# InclinometerPower.net
KiCad netlist of a schematic drawn in Altium Designer
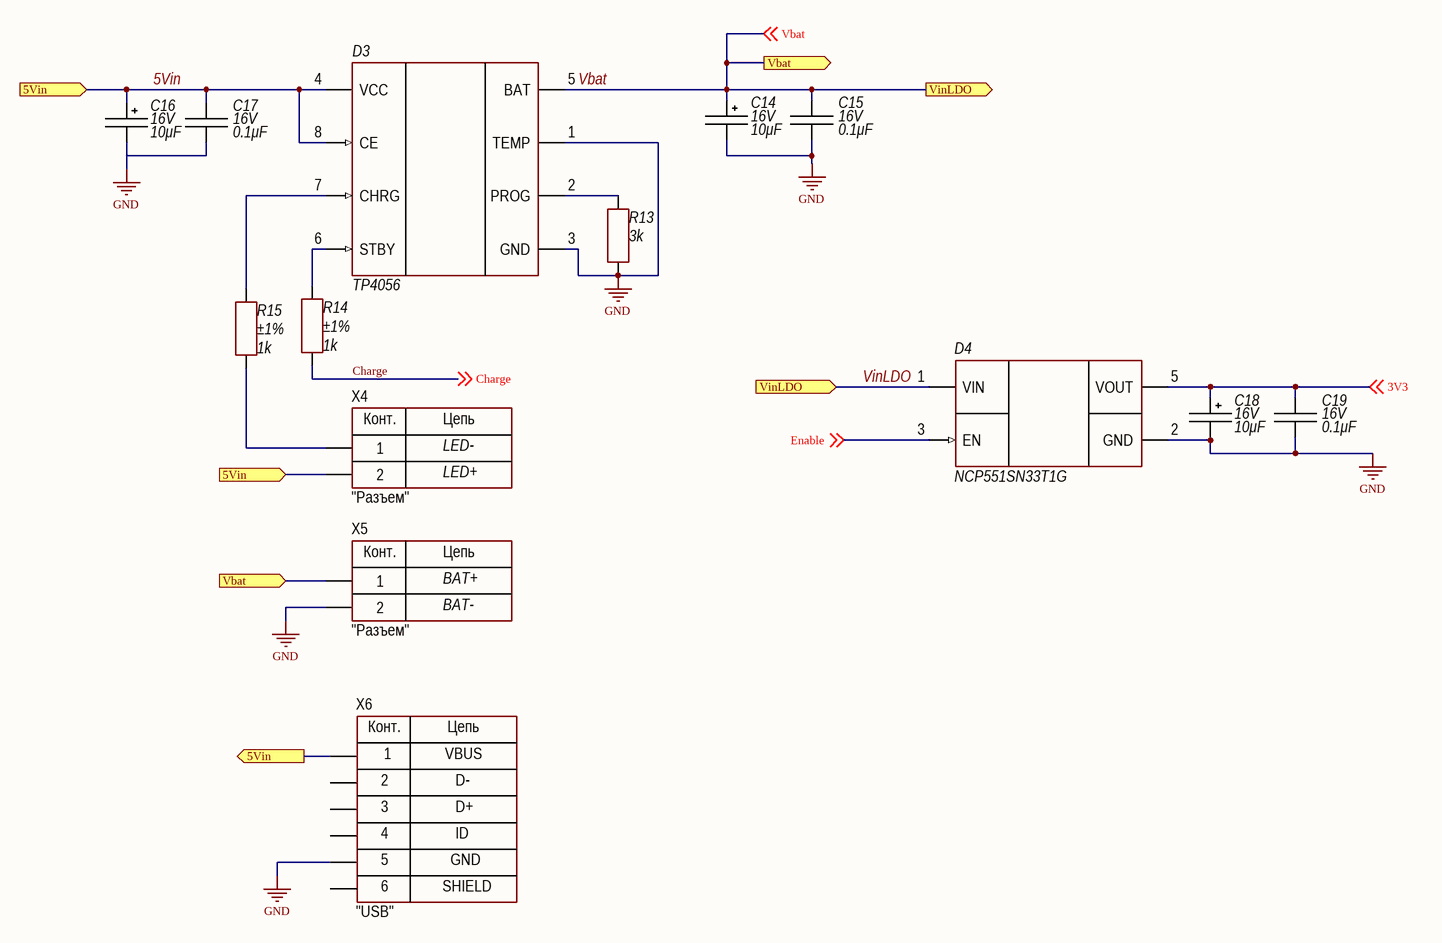
[diagram p0: InclinometerPower.SchDoc]

(export (version "E")
  (design (tool "Eeschema 10.0.6"))
  (components
    (comp (ref "C14")
      (value "10μF")
      (footprint "CAP: TANTAL-A")
      (fields
        (field (name "MANUFACTURER") "AVX")
        (field (name "PARTNUMBER") "TAJA106K016RNJ")
        (field (name "VALUEMANUFACTURERPARTNUMBER") "Tantalum capacitor, 10μF, 16V, ±10%, 3Ohm, case A (3216), -55...+125°C")
        (field (name "VOLTAGE") "16V")
      )
      (libsource (lib "") (part "Tantal_A_1"))
    )
    (comp (ref "C15")
      (value "0.1μF")
      (footprint "CAP: 0603")
      (fields
        (field (name "MANUFACTURER") "Murata Electronics")
        (field (name "PARTNUMBER") "GRM188R71C104KA01D")
        (field (name "VALUEMANUFACTURERPARTNUMBER") "Ceramic capacitor, 0.1μF, X7R, ±10%, 16V, 0603, -55...+125°C")
        (field (name "VOLTAGE") "16V")
      )
      (libsource (lib "") (part "Ceramic_0603_1"))
    )
    (comp (ref "C16")
      (value "10μF")
      (footprint "CAP: TANTAL-A")
      (fields
        (field (name "MANUFACTURER") "AVX")
        (field (name "PARTNUMBER") "TAJA106K016RNJ")
        (field (name "VALUEMANUFACTURERPARTNUMBER") "Tantalum capacitor, 10μF, 16V, ±10%, 3Ohm, case A (3216), -55...+125°C")
        (field (name "VOLTAGE") "16V")
      )
      (libsource (lib "Capacitor") (part "Tantal_A"))
    )
    (comp (ref "C17")
      (value "0.1μF")
      (footprint "CAP: 0603")
      (fields
        (field (name "MANUFACTURER") "Murata Electronics")
        (field (name "PARTNUMBER") "GRM188R71C104KA01D")
        (field (name "VALUEMANUFACTURERPARTNUMBER") "Ceramic capacitor, 0.1μF, X7R, ±10%, 16V, 0603, -55...+125°C")
        (field (name "VOLTAGE") "16V")
      )
      (libsource (lib "Capacitor") (part "Ceramic_0603"))
    )
    (comp (ref "C18")
      (value "10μF")
      (footprint "CAP: TANTAL-A")
      (fields
        (field (name "MANUFACTURER") "AVX")
        (field (name "PARTNUMBER") "TAJA106K016RNJ")
        (field (name "VALUEMANUFACTURERPARTNUMBER") "Tantalum capacitor, 10μF, 16V, ±10%, 3Ohm, case A (3216), -55...+125°C")
        (field (name "VOLTAGE") "16V")
      )
      (libsource (lib "") (part "Tantal_A_1"))
    )
    (comp (ref "C19")
      (value "0.1μF")
      (footprint "CAP: 0603")
      (fields
        (field (name "MANUFACTURER") "Murata Electronics")
        (field (name "PARTNUMBER") "GRM188R71C104KA01D")
        (field (name "VALUEMANUFACTURERPARTNUMBER") "Ceramic capacitor, 0.1μF, X7R, ±10%, 16V, 0603, -55...+125°C")
        (field (name "VOLTAGE") "16V")
      )
      (libsource (lib "") (part "Ceramic_0603_1"))
    )
    (comp (ref "D3")
      (value "~")
      (footprint "SOP8")
      (description "Linear Li-lon Battery Charger")
      (fields
        (field (name "MANUFACTURER") "Top Power")
        (field (name "VALUEMANUFACTURERPARTNUMBER") "Linear Li-lon Battery Charger, , , , 1A, -40...+85°C, SOP-8")
        (field (name "PARTNUMBER") "TP4056")
      )
      (libsource (lib "IC. Power supply") (part "TP4056"))
    )
    (comp (ref "D4")
      (value "~")
      (footprint "5-TSOP")
      (description "Linear voltage regulator")
      (fields
        (field (name "MANUFACTURER") "ON Semiconductor")
        (field (name "VALUEMANUFACTURERPARTNUMBER") "Linear voltage regulator, input 0...12V, 0.25V, output 3.3V, 150mA, -40...+85°C, TSOP-5")
        (field (name "PARTNUMBER") "NCP551SN33T1G")
      )
      (libsource (lib "IC. Power supply") (part "NCP551SN33T1G"))
    )
    (comp (ref "R13")
      (value "3k")
      (footprint "RES: 0603")
      (fields
        (field (name "MANUFACTURER") "Yageo")
        (field (name "PARTNUMBER") "RC0603FR-073KL")
        (field (name "VALUEMANUFACTURERPARTNUMBER") "Resistor film, 3k, ±1%, 0603, 0.1W, -55...+155°C")
      )
      (libsource (lib "Resistor") (part "Resistor_0603"))
    )
    (comp (ref "R14")
      (value "1k")
      (footprint "RES: 0603")
      (fields
        (field (name "MANUFACTURER") "Yageo")
        (field (name "PARTNUMBER") "RC0603FR-071KL")
        (field (name "VALUEMANUFACTURERPARTNUMBER") "Resistor film, 1k, ±1%, 0603, 0.1W, -55...+155°C")
        (field (name "TOLERANCE") "±1%")
      )
      (libsource (lib "") (part "Resistor_0603_1"))
    )
    (comp (ref "R15")
      (value "1k")
      (footprint "RES: 0603")
      (fields
        (field (name "MANUFACTURER") "Yageo")
        (field (name "PARTNUMBER") "RC0603FR-071KL")
        (field (name "VALUEMANUFACTURERPARTNUMBER") "Resistor film, 1k, ±1%, 0603, 0.1W, -55...+155°C")
        (field (name "TOLERANCE") "±1%")
      )
      (libsource (lib "Resistor") (part "Resistor_0603"))
    )
    (comp (ref "X4")
      (value "~")
      (footprint "CON: PLS-2")
      (fields
        (field (name "MANUFACTURER") "Connfly")
        (field (name "VALUEMANUFACTURERPARTNUMBER") "Connector, 2pin, 2.54mm, 500VAC, 3A")
        (field (name "PARTNUMBER") "PLS-2")
        (field (name "COMMENTTEXT") "\"Разъем\"")
      )
      (libsource (lib "Connector") (part "PLS-2"))
    )
    (comp (ref "X5")
      (value "~")
      (footprint "CON: PLS-2")
      (fields
        (field (name "MANUFACTURER") "Connfly")
        (field (name "VALUEMANUFACTURERPARTNUMBER") "Connector, 2pin, 2.54mm, 500VAC, 3A")
        (field (name "PARTNUMBER") "PLS-2")
        (field (name "COMMENTTEXT") "\"Разъем\"")
      )
      (libsource (lib "Connector") (part "PLS-2"))
    )
    (comp (ref "X6")
      (value "~")
      (footprint "CON: USB micro-A (ZX62-B-5PA)")
      (fields
        (field (name "MANUFACTURER") "Hirose Electric")
        (field (name "VALUEMANUFACTURERPARTNUMBER") "USB micro B")
        (field (name "PARTNUMBER") "ZX62-B-5PA")
        (field (name "COMMENTTEXT") "\"USB\"")
      )
      (libsource (lib "Connector") (part "Connector_USB_micro_B"))
    )
  )
  (nets
    (net (code "1") (name "/5Vin") (class "Default")
      (node (ref "C16") (pin "1") (pinfunction "1_1") (pintype "power_in"))
      (node (ref "C17") (pin "2") (pinfunction "2_2") (pintype "power_in"))
      (node (ref "D3") (pin "4") (pinfunction "VCC_4") (pintype "power_in"))
      (node (ref "D3") (pin "8") (pinfunction "CE_8") (pintype "input"))
      (node (ref "X4") (pin "2") (pinfunction "2_2") (pintype "passive"))
      (node (ref "X6") (pin "1") (pintype "passive"))
    )
    (net (code "2") (name "3V3") (class "Default")
      (node (ref "C18") (pin "1") (pinfunction "1_1") (pintype "power_in"))
      (node (ref "C19") (pin "2") (pinfunction "2_2") (pintype "power_in"))
      (node (ref "D4") (pin "5") (pinfunction "VOUT_5") (pintype "power_in"))
    )
    (net (code "3") (name "Charge") (class "Default")
      (node (ref "R14") (pin "1") (pinfunction "1_1") (pintype "passive"))
    )
    (net (code "4") (name "Enable") (class "Default")
      (node (ref "D4") (pin "3") (pinfunction "EN_3") (pintype "input"))
    )
    (net (code "5") (name "GND") (class "Default")
      (node (ref "C14") (pin "2") (pinfunction "2_2") (pintype "power_in"))
      (node (ref "C15") (pin "1") (pinfunction "1_1") (pintype "power_in"))
      (node (ref "C16") (pin "2") (pinfunction "2_2") (pintype "power_in"))
      (node (ref "C17") (pin "1") (pinfunction "1_1") (pintype "power_in"))
      (node (ref "C18") (pin "2") (pinfunction "2_2") (pintype "power_in"))
      (node (ref "C19") (pin "1") (pinfunction "1_1") (pintype "power_in"))
      (node (ref "D3") (pin "1") (pinfunction "TEMP_1") (pintype "passive"))
      (node (ref "D3") (pin "3") (pinfunction "GND_3") (pintype "power_in"))
      (node (ref "D4") (pin "2") (pinfunction "GND_2") (pintype "power_in"))
      (node (ref "R13") (pin "1") (pinfunction "1_1") (pintype "passive"))
      (node (ref "X5") (pin "2") (pinfunction "2_2") (pintype "passive"))
      (node (ref "X6") (pin "5") (pinfunction "5_5") (pintype "passive"))
    )
    (net (code "6") (name "Net-(D3-CHRG)") (class "Default")
      (node (ref "D3") (pin "7") (pinfunction "CHRG_7") (pintype "input"))
      (node (ref "R15") (pin "2") (pinfunction "2_2") (pintype "passive"))
    )
    (net (code "7") (name "Net-(D3-PROG)") (class "Default")
      (node (ref "D3") (pin "2") (pinfunction "PROG_2") (pintype "passive"))
      (node (ref "R13") (pin "2") (pinfunction "2_2") (pintype "passive"))
    )
    (net (code "8") (name "Net-(D3-STBY)") (class "Default")
      (node (ref "D3") (pin "6") (pinfunction "STBY_6") (pintype "input"))
      (node (ref "R14") (pin "2") (pinfunction "2_2") (pintype "passive"))
    )
    (net (code "9") (name "Net-(R15-Pad1)") (class "Default")
      (node (ref "R15") (pin "1") (pinfunction "1_1") (pintype "passive"))
      (node (ref "X4") (pin "1") (pinfunction "1_1") (pintype "passive"))
    )
    (net (code "10") (name "Vbat") (class "Default")
      (node (ref "C14") (pin "1") (pinfunction "1_1") (pintype "power_in"))
      (node (ref "C15") (pin "2") (pinfunction "2_2") (pintype "power_in"))
      (node (ref "D3") (pin "5") (pinfunction "BAT_5") (pintype "power_in"))
      (node (ref "D4") (pin "1") (pinfunction "VIN_1") (pintype "power_in"))
      (node (ref "X5") (pin "1") (pinfunction "1_1") (pintype "passive"))
    )
    (net (code "11") (name "unconnected-(X6-Pad0)") (class "Default")
      (node (ref "X6") (pin "0") (pinfunction "0_0") (pintype "passive"))
    )
    (net (code "12") (name "unconnected-(X6-Pad2)") (class "Default")
      (node (ref "X6") (pin "2") (pinfunction "2_2") (pintype "passive"))
    )
    (net (code "13") (name "unconnected-(X6-Pad3)") (class "Default")
      (node (ref "X6") (pin "3") (pinfunction "3_3") (pintype "passive"))
    )
    (net (code "14") (name "unconnected-(X6-Pad4)") (class "Default")
      (node (ref "X6") (pin "4") (pinfunction "4_4") (pintype "passive"))
    )
  )
)
